# MEMS_ADC.net
KiCad netlist of a schematic drawn in EAGLE
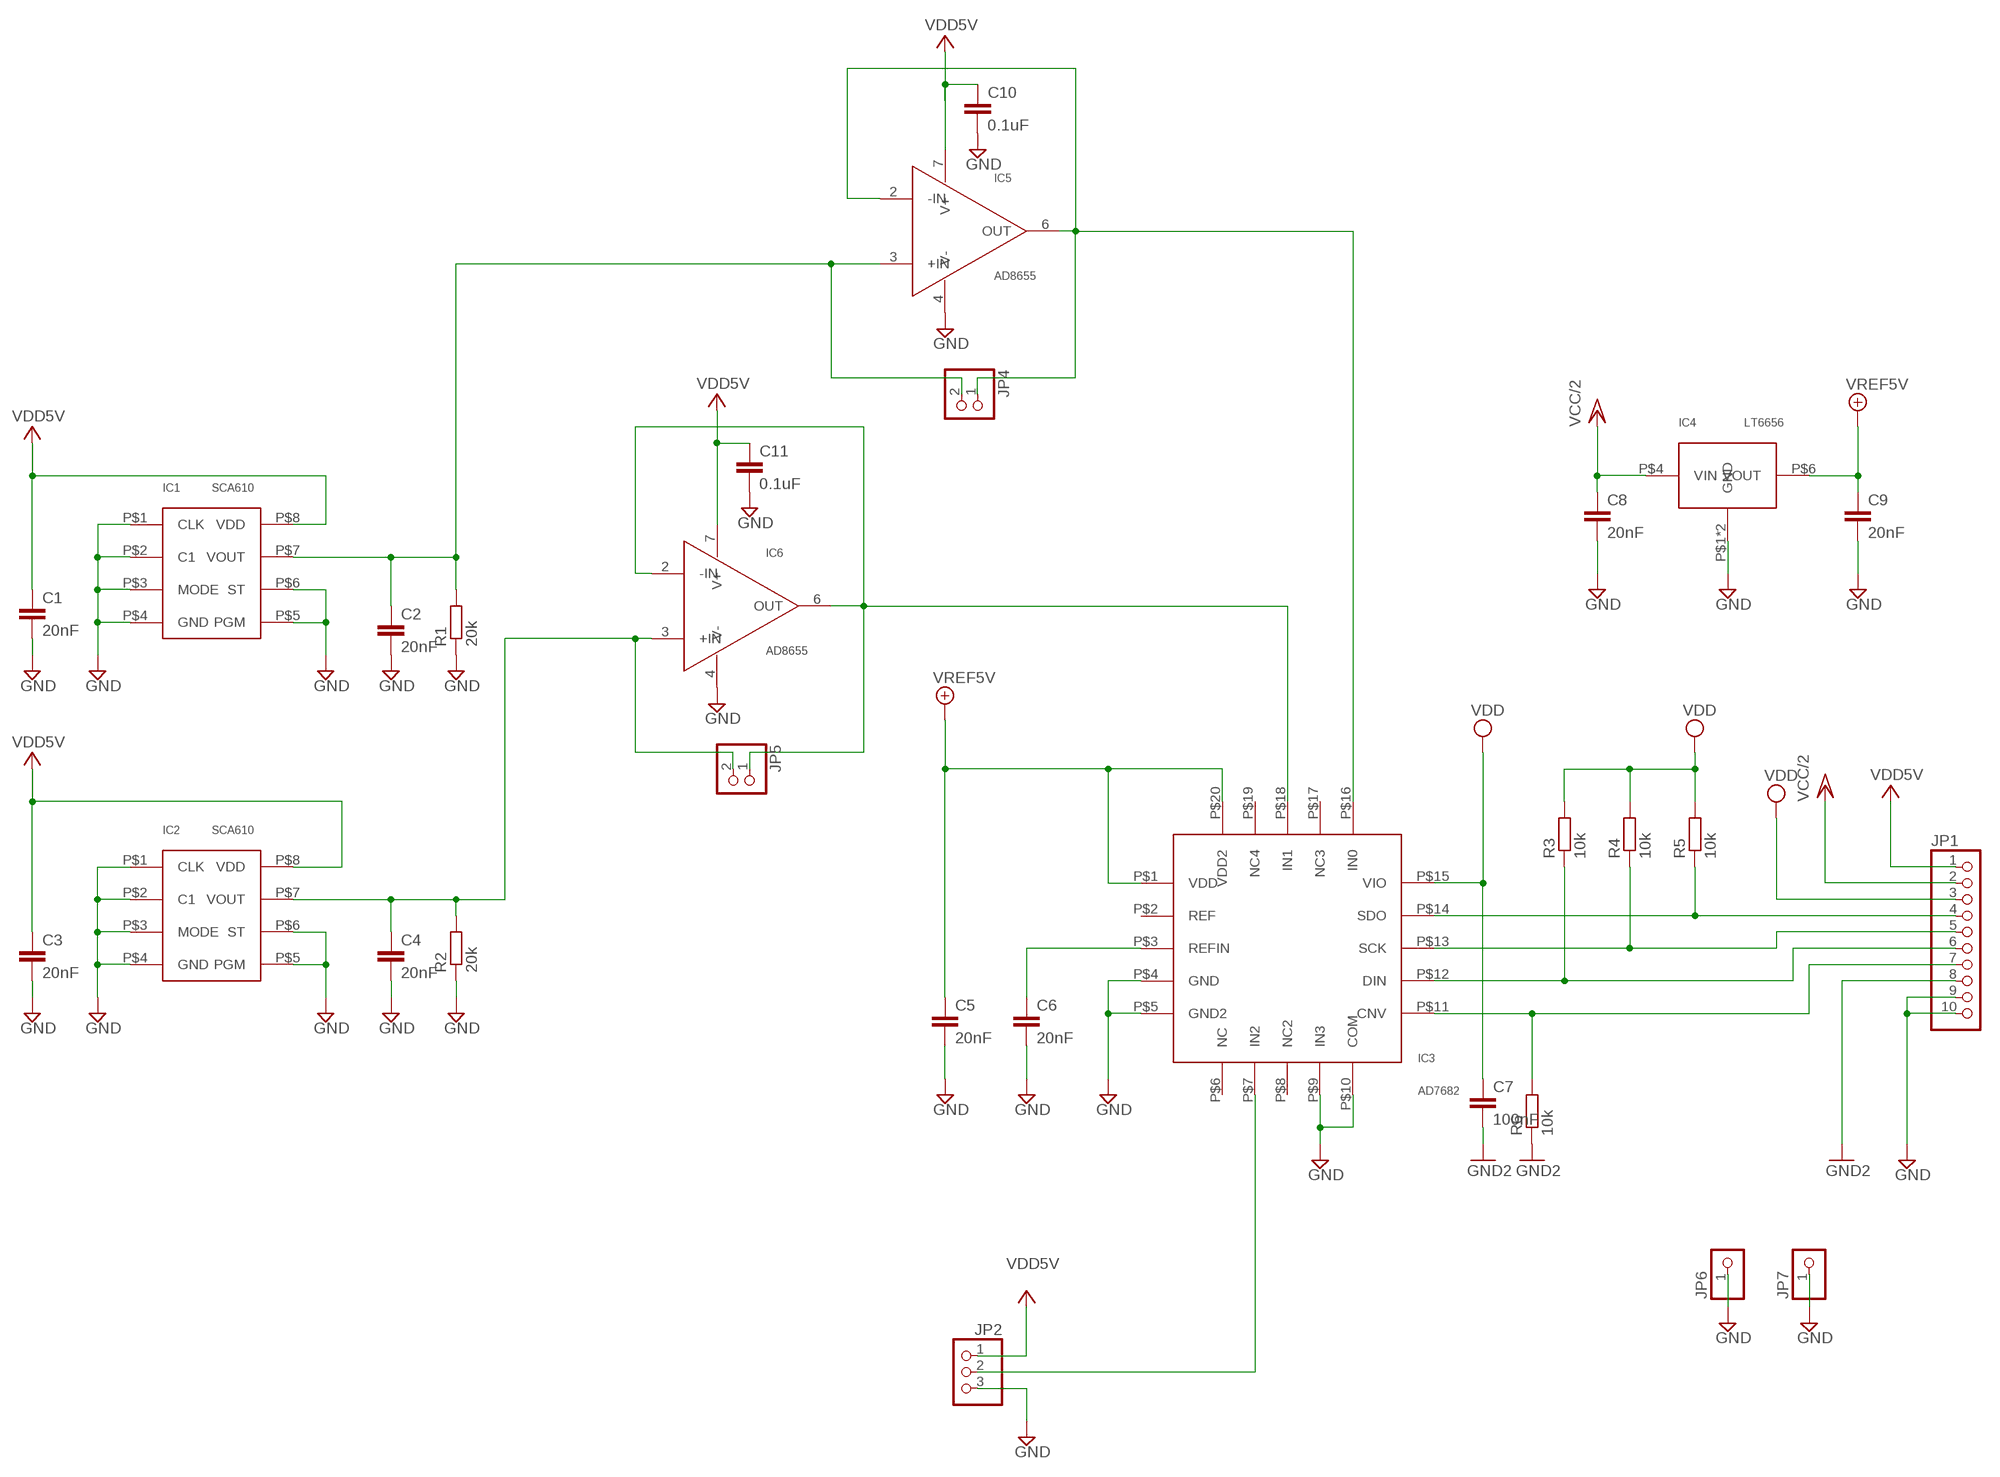
[diagram p0: schematic, sheet 1]

(export (version "E")
  (design (tool "Eeschema 10.0.6"))
  (components
    (comp (ref "C1")
      (value "20nF")
      (footprint "eagle-import:C0805")
      (libsource (lib "eagle-import") (part "C-EUC0805"))
    )
    (comp (ref "C2")
      (value "20nF")
      (footprint "eagle-import:C0805")
      (libsource (lib "eagle-import") (part "C-EUC0805"))
    )
    (comp (ref "C3")
      (value "20nF")
      (footprint "eagle-import:C0805")
      (libsource (lib "eagle-import") (part "C-EUC0805"))
    )
    (comp (ref "C4")
      (value "20nF")
      (footprint "eagle-import:C0805")
      (libsource (lib "eagle-import") (part "C-EUC0805"))
    )
    (comp (ref "C5")
      (value "20nF")
      (footprint "eagle-import:C0805")
      (libsource (lib "eagle-import") (part "C-EUC0805"))
    )
    (comp (ref "C6")
      (value "20nF")
      (footprint "eagle-import:C0805")
      (libsource (lib "eagle-import") (part "C-EUC0805"))
    )
    (comp (ref "C7")
      (value "100nF")
      (footprint "eagle-import:C0805")
      (libsource (lib "eagle-import") (part "C-EUC0805"))
    )
    (comp (ref "C8")
      (value "20nF")
      (footprint "eagle-import:C0805")
      (libsource (lib "eagle-import") (part "C-EUC0805"))
    )
    (comp (ref "C9")
      (value "20nF")
      (footprint "eagle-import:C0805")
      (libsource (lib "eagle-import") (part "C-EUC0805"))
    )
    (comp (ref "C10")
      (value "0.1uF")
      (footprint "eagle-import:C0805")
      (libsource (lib "eagle-import") (part "C-EUC0805"))
    )
    (comp (ref "C11")
      (value "0.1uF")
      (footprint "eagle-import:C0805")
      (libsource (lib "eagle-import") (part "C-EUC0805"))
    )
    (comp (ref "IC1")
      (value "SCA610")
      (footprint "eagle-import:SCA610-D14H1")
      (libsource (lib "eagle-import") (part "SCA610-D14H11"))
    )
    (comp (ref "IC2")
      (value "SCA610")
      (footprint "eagle-import:SCA610-D14H1")
      (libsource (lib "eagle-import") (part "SCA610-D14H11"))
    )
    (comp (ref "IC3")
      (value "AD7682")
      (footprint "eagle-import:AD7682")
      (libsource (lib "eagle-import") (part "AD7682"))
    )
    (comp (ref "IC4")
      (value "LT6656")
      (footprint "eagle-import:SOT23-6")
      (libsource (lib "eagle-import") (part "LT6656"))
    )
    (comp (ref "IC5")
      (value "AD8655")
      (footprint "eagle-import:SOIC8")
      (libsource (lib "eagle-import") (part "AD8655"))
    )
    (comp (ref "IC6")
      (value "AD8655")
      (footprint "eagle-import:SOIC8")
      (libsource (lib "eagle-import") (part "AD8655"))
    )
    (comp (ref "JP1")
      (value "PINHD-1X10")
      (footprint "eagle-import:1X10")
      (libsource (lib "eagle-import") (part "PINHD-1X10"))
    )
    (comp (ref "JP2")
      (value "PINHD-1X3")
      (footprint "eagle-import:1X03")
      (libsource (lib "eagle-import") (part "PINHD-1X3"))
    )
    (comp (ref "JP4")
      (value "PINHD-1X2")
      (footprint "eagle-import:1X02")
      (libsource (lib "eagle-import") (part "PINHD-1X2"))
    )
    (comp (ref "JP5")
      (value "PINHD-1X2")
      (footprint "eagle-import:1X02")
      (libsource (lib "eagle-import") (part "PINHD-1X2"))
    )
    (comp (ref "JP6")
      (value "PINHD-1X1")
      (footprint "eagle-import:1X01")
      (libsource (lib "eagle-import") (part "PINHD-1X1"))
    )
    (comp (ref "JP7")
      (value "PINHD-1X1")
      (footprint "eagle-import:1X01")
      (libsource (lib "eagle-import") (part "PINHD-1X1"))
    )
    (comp (ref "R1")
      (value "20k")
      (footprint "eagle-import:R0805")
      (libsource (lib "eagle-import") (part "R-EU_R0805"))
    )
    (comp (ref "R2")
      (value "20k")
      (footprint "eagle-import:R0805")
      (libsource (lib "eagle-import") (part "R-EU_R0805"))
    )
    (comp (ref "R3")
      (value "10k")
      (footprint "eagle-import:R0805")
      (libsource (lib "eagle-import") (part "R-EU_R0805"))
    )
    (comp (ref "R4")
      (value "10k")
      (footprint "eagle-import:R0805")
      (libsource (lib "eagle-import") (part "R-EU_R0805"))
    )
    (comp (ref "R5")
      (value "10k")
      (footprint "eagle-import:R0805")
      (libsource (lib "eagle-import") (part "R-EU_R0805"))
    )
    (comp (ref "R6")
      (value "10k")
      (footprint "eagle-import:R0805")
      (libsource (lib "eagle-import") (part "R-EU_R0805"))
    )
  )
  (nets
    (net (code "1") (name "GND") (class "Default")
      (node (ref "C1") (pin "2") (pinfunction "2_2") (pintype "passive"))
      (node (ref "C10") (pin "2") (pinfunction "2_2") (pintype "passive"))
      (node (ref "C11") (pin "2") (pinfunction "2_2") (pintype "passive"))
      (node (ref "C2") (pin "2") (pinfunction "2_2") (pintype "passive"))
      (node (ref "C3") (pin "2") (pinfunction "2_2") (pintype "passive"))
      (node (ref "C4") (pin "2") (pinfunction "2_2") (pintype "passive"))
      (node (ref "C5") (pin "2") (pinfunction "2_2") (pintype "passive"))
      (node (ref "C6") (pin "2") (pinfunction "2_2") (pintype "passive"))
      (node (ref "C7") (pin "2") (pinfunction "2_2") (pintype "passive"))
      (node (ref "C8") (pin "2") (pinfunction "2_2") (pintype "passive"))
      (node (ref "C9") (pin "2") (pinfunction "2_2") (pintype "passive"))
      (node (ref "IC1") (pin "P$1") (pinfunction "CLK_P$1") (pintype "bidirectional"))
      (node (ref "IC1") (pin "P$2") (pinfunction "C1_P$2") (pintype "bidirectional"))
      (node (ref "IC1") (pin "P$3") (pinfunction "MODE_P$3") (pintype "bidirectional"))
      (node (ref "IC1") (pin "P$4") (pinfunction "GND_P$4") (pintype "bidirectional"))
      (node (ref "IC1") (pin "P$5") (pinfunction "PGM_P$5") (pintype "bidirectional"))
      (node (ref "IC1") (pin "P$6") (pinfunction "ST_P$6") (pintype "bidirectional"))
      (node (ref "IC2") (pin "P$1") (pinfunction "CLK_P$1") (pintype "bidirectional"))
      (node (ref "IC2") (pin "P$2") (pinfunction "C1_P$2") (pintype "bidirectional"))
      (node (ref "IC2") (pin "P$3") (pinfunction "MODE_P$3") (pintype "bidirectional"))
      (node (ref "IC2") (pin "P$4") (pinfunction "GND_P$4") (pintype "bidirectional"))
      (node (ref "IC2") (pin "P$5") (pinfunction "PGM_P$5") (pintype "bidirectional"))
      (node (ref "IC2") (pin "P$6") (pinfunction "ST_P$6") (pintype "bidirectional"))
      (node (ref "IC3") (pin "P$10") (pinfunction "COM_P$10") (pintype "bidirectional"))
      (node (ref "IC3") (pin "P$4") (pinfunction "GND_P$4") (pintype "bidirectional"))
      (node (ref "IC3") (pin "P$5") (pinfunction "GND2_P$5") (pintype "bidirectional"))
      (node (ref "IC3") (pin "P$9") (pinfunction "IN3_P$9") (pintype "bidirectional"))
      (node (ref "IC4") (pin "P$1") (pinfunction "GND_P$1") (pintype "bidirectional"))
      (node (ref "IC4") (pin "P$2") (pinfunction "GND_P$2") (pintype "bidirectional"))
      (node (ref "IC5") (pin "4") (pinfunction "V-_4") (pintype "bidirectional"))
      (node (ref "IC6") (pin "4") (pinfunction "V-_4") (pintype "bidirectional"))
      (node (ref "JP1") (pin "10") (pinfunction "10_10") (pintype "passive"))
      (node (ref "JP1") (pin "8") (pinfunction "8_8") (pintype "passive"))
      (node (ref "JP1") (pin "9") (pinfunction "9_9") (pintype "passive"))
      (node (ref "JP2") (pin "3") (pinfunction "3_3") (pintype "passive"))
      (node (ref "JP6") (pin "1") (pinfunction "1_1") (pintype "passive"))
      (node (ref "JP7") (pin "1") (pinfunction "1_1") (pintype "passive"))
      (node (ref "R1") (pin "1") (pinfunction "1_1") (pintype "passive"))
      (node (ref "R2") (pin "1") (pinfunction "1_1") (pintype "passive"))
      (node (ref "R6") (pin "1") (pinfunction "1_1") (pintype "passive"))
    )
    (net (code "2") (name "Net-(IC1-VOUT)") (class "Default")
      (node (ref "C2") (pin "1") (pinfunction "1_1") (pintype "passive"))
      (node (ref "IC1") (pin "P$7") (pinfunction "VOUT_P$7") (pintype "bidirectional"))
      (node (ref "IC5") (pin "3") (pinfunction "+IN_3") (pintype "bidirectional"))
      (node (ref "JP4") (pin "2") (pinfunction "2_2") (pintype "passive"))
      (node (ref "R1") (pin "2") (pinfunction "2_2") (pintype "passive"))
    )
    (net (code "3") (name "Net-(IC2-VOUT)") (class "Default")
      (node (ref "C4") (pin "1") (pinfunction "1_1") (pintype "passive"))
      (node (ref "IC2") (pin "P$7") (pinfunction "VOUT_P$7") (pintype "bidirectional"))
      (node (ref "IC6") (pin "3") (pinfunction "+IN_3") (pintype "bidirectional"))
      (node (ref "JP5") (pin "2") (pinfunction "2_2") (pintype "passive"))
      (node (ref "R2") (pin "2") (pinfunction "2_2") (pintype "passive"))
    )
    (net (code "4") (name "Net-(IC3-CNV)") (class "Default")
      (node (ref "IC3") (pin "P$11") (pinfunction "CNV_P$11") (pintype "bidirectional"))
      (node (ref "JP1") (pin "7") (pinfunction "7_7") (pintype "passive"))
      (node (ref "R6") (pin "2") (pinfunction "2_2") (pintype "passive"))
    )
    (net (code "5") (name "Net-(IC3-DIN)") (class "Default")
      (node (ref "IC3") (pin "P$12") (pinfunction "DIN_P$12") (pintype "bidirectional"))
      (node (ref "JP1") (pin "6") (pinfunction "6_6") (pintype "passive"))
      (node (ref "R3") (pin "1") (pinfunction "1_1") (pintype "passive"))
    )
    (net (code "6") (name "Net-(IC3-IN0)") (class "Default")
      (node (ref "IC3") (pin "P$16") (pinfunction "IN0_P$16") (pintype "bidirectional"))
      (node (ref "IC5") (pin "2") (pinfunction "-IN_2") (pintype "bidirectional"))
      (node (ref "IC5") (pin "6") (pinfunction "OUT_6") (pintype "bidirectional"))
      (node (ref "JP4") (pin "1") (pinfunction "1_1") (pintype "passive"))
    )
    (net (code "7") (name "Net-(IC3-IN1)") (class "Default")
      (node (ref "IC3") (pin "P$18") (pinfunction "IN1_P$18") (pintype "bidirectional"))
      (node (ref "IC6") (pin "2") (pinfunction "-IN_2") (pintype "bidirectional"))
      (node (ref "IC6") (pin "6") (pinfunction "OUT_6") (pintype "bidirectional"))
      (node (ref "JP5") (pin "1") (pinfunction "1_1") (pintype "passive"))
    )
    (net (code "8") (name "Net-(IC3-IN2)") (class "Default")
      (node (ref "IC3") (pin "P$7") (pinfunction "IN2_P$7") (pintype "bidirectional"))
      (node (ref "JP2") (pin "2") (pinfunction "2_2") (pintype "passive"))
    )
    (net (code "9") (name "Net-(IC3-REFIN)") (class "Default")
      (node (ref "C6") (pin "1") (pinfunction "1_1") (pintype "passive"))
      (node (ref "IC3") (pin "P$3") (pinfunction "REFIN_P$3") (pintype "bidirectional"))
    )
    (net (code "10") (name "Net-(IC3-SCK)") (class "Default")
      (node (ref "IC3") (pin "P$13") (pinfunction "SCK_P$13") (pintype "bidirectional"))
      (node (ref "JP1") (pin "5") (pinfunction "5_5") (pintype "passive"))
      (node (ref "R4") (pin "1") (pinfunction "1_1") (pintype "passive"))
    )
    (net (code "11") (name "Net-(IC3-SDO)") (class "Default")
      (node (ref "IC3") (pin "P$14") (pinfunction "SDO_P$14") (pintype "bidirectional"))
      (node (ref "JP1") (pin "4") (pinfunction "4_4") (pintype "passive"))
      (node (ref "R5") (pin "1") (pinfunction "1_1") (pintype "passive"))
    )
    (net (code "12") (name "VCC{slash}2") (class "Default")
      (node (ref "C8") (pin "1") (pinfunction "1_1") (pintype "passive"))
      (node (ref "IC4") (pin "P$4") (pinfunction "VIN_P$4") (pintype "bidirectional"))
      (node (ref "JP1") (pin "2") (pinfunction "2_2") (pintype "passive"))
    )
    (net (code "13") (name "VDD") (class "Default")
      (node (ref "C7") (pin "1") (pinfunction "1_1") (pintype "passive"))
      (node (ref "IC3") (pin "P$15") (pinfunction "VIO_P$15") (pintype "bidirectional"))
      (node (ref "JP1") (pin "3") (pinfunction "3_3") (pintype "passive"))
      (node (ref "R3") (pin "2") (pinfunction "2_2") (pintype "passive"))
      (node (ref "R4") (pin "2") (pinfunction "2_2") (pintype "passive"))
      (node (ref "R5") (pin "2") (pinfunction "2_2") (pintype "passive"))
    )
    (net (code "14") (name "VDD5V") (class "Default")
      (node (ref "C1") (pin "1") (pinfunction "1_1") (pintype "passive"))
      (node (ref "C10") (pin "1") (pinfunction "1_1") (pintype "passive"))
      (node (ref "C11") (pin "1") (pinfunction "1_1") (pintype "passive"))
      (node (ref "C3") (pin "1") (pinfunction "1_1") (pintype "passive"))
      (node (ref "IC1") (pin "P$8") (pinfunction "VDD_P$8") (pintype "bidirectional"))
      (node (ref "IC2") (pin "P$8") (pinfunction "VDD_P$8") (pintype "bidirectional"))
      (node (ref "IC5") (pin "7") (pinfunction "V+_7") (pintype "bidirectional"))
      (node (ref "IC6") (pin "7") (pinfunction "V+_7") (pintype "bidirectional"))
      (node (ref "JP1") (pin "1") (pinfunction "1_1") (pintype "passive"))
      (node (ref "JP2") (pin "1") (pinfunction "1_1") (pintype "passive"))
    )
    (net (code "15") (name "VREF5V") (class "Default")
      (node (ref "C5") (pin "1") (pinfunction "1_1") (pintype "passive"))
      (node (ref "C9") (pin "1") (pinfunction "1_1") (pintype "passive"))
      (node (ref "IC3") (pin "P$1") (pinfunction "VDD_P$1") (pintype "bidirectional"))
      (node (ref "IC3") (pin "P$20") (pinfunction "VDD2_P$20") (pintype "bidirectional"))
      (node (ref "IC4") (pin "P$6") (pinfunction "VOUT_P$6") (pintype "bidirectional"))
    )
    (net (code "16") (name "unconnected-(IC3-NC-PadP$6)") (class "Default")
      (node (ref "IC3") (pin "P$6") (pinfunction "NC_P$6") (pintype "bidirectional"))
    )
    (net (code "17") (name "unconnected-(IC3-NC2-PadP$8)") (class "Default")
      (node (ref "IC3") (pin "P$8") (pinfunction "NC2_P$8") (pintype "bidirectional"))
    )
    (net (code "18") (name "unconnected-(IC3-NC3-PadP$17)") (class "Default")
      (node (ref "IC3") (pin "P$17") (pinfunction "NC3_P$17") (pintype "bidirectional"))
    )
    (net (code "19") (name "unconnected-(IC3-NC4-PadP$19)") (class "Default")
      (node (ref "IC3") (pin "P$19") (pinfunction "NC4_P$19") (pintype "bidirectional"))
    )
    (net (code "20") (name "unconnected-(IC3-REF-PadP$2)") (class "Default")
      (node (ref "IC3") (pin "P$2") (pinfunction "REF_P$2") (pintype "bidirectional"))
    )
  )
)
